# Ethernet.net
KiCad netlist of a schematic drawn in Altium Designer
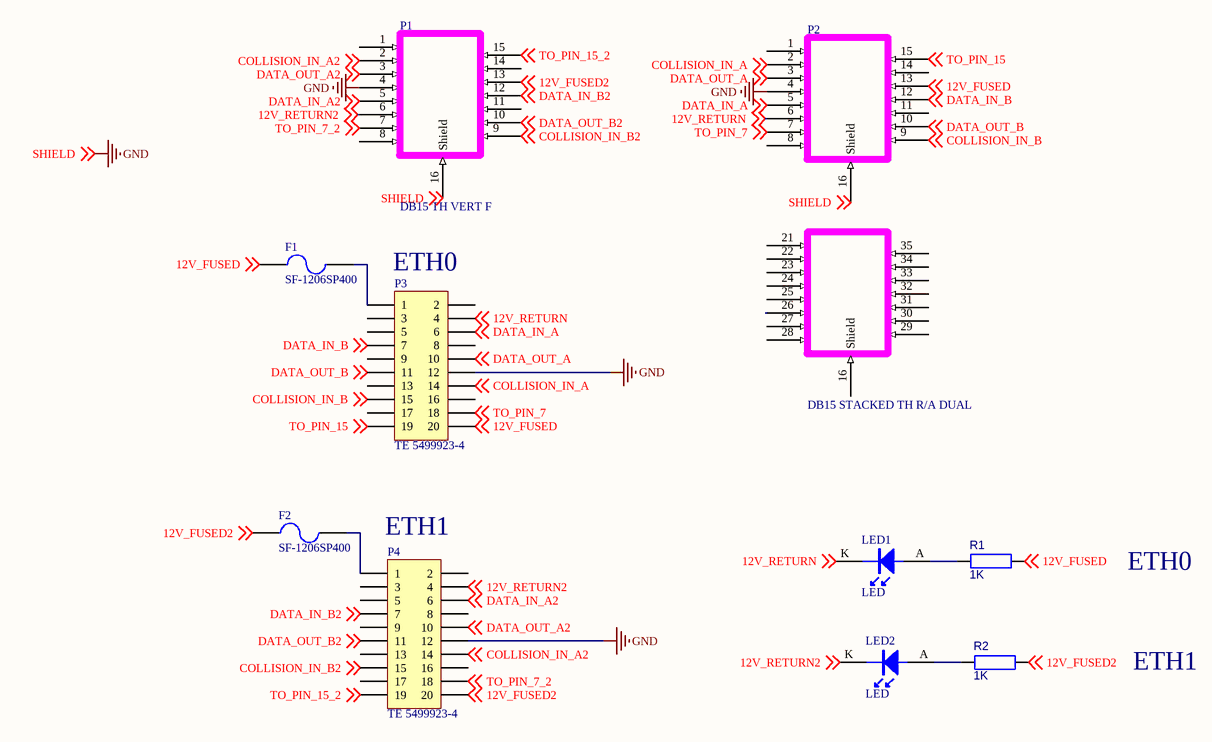
[diagram p0: Ethernet.SchDoc]

(export (version "E")
  (design (tool "Eeschema 10.0.6"))
  (components
    (comp (ref "F1")
      (value "SF-1206SP400")
      (footprint "F1206SB")
      (description "Fuse 4A")
      (fields (field (name "PUBLISHER") "Altium Limited"))
      (libsource (lib "Kanitti") (part "Fuse 2"))
    )
    (comp (ref "F2")
      (value "SF-1206SP400")
      (footprint "F1206SB")
      (description "Fuse 4A")
      (fields (field (name "PUBLISHER") "Altium Limited"))
      (libsource (lib "Kanitti") (part "Fuse 2"))
    )
    (comp (ref "LED1") (value "LED") (footprint "LTST-C170") (libsource (lib "TRA1404(DIFT2)") (part "LED")))
    (comp (ref "LED2") (value "LED") (footprint "LTST-C170") (libsource (lib "TRA1404(DIFT2)") (part "LED")))
    (comp (ref "P1")
      (value "DB15 TH VERT F")
      (footprint "D15S24A4GV00LF")
      (libsource (lib "Kanitti") (part "DB15 TH VERT F"))
    )
    (comp (ref "P2")
      (value "DB15 STACKED TH R/A DUAL")
      (footprint "189-015-513R571")
      (libsource (lib "Kanitti") (part "DB15 STACKED TH R/A DUAL"))
    )
    (comp (ref "P3")
      (value "TE 5499923-4")
      (footprint "HDR2X10 - Small Pads")
      (description "Header, 20-Pin, Dual row")
      (fields (field (name "PUBLISHER") "Altium Limited"))
      (libsource (lib "Kanitti") (part "Header 10X2"))
    )
    (comp (ref "P4")
      (value "TE 5499923-4")
      (footprint "HDR2X10 - Small Pads")
      (description "Header, 20-Pin, Dual row")
      (fields (field (name "PUBLISHER") "Altium Limited"))
      (libsource (lib "Kanitti") (part "Header 10X2"))
    )
    (comp (ref "R1")
      (value "1K")
      (footprint "RESC2012X70N")
      (description "RESISTOR")
      (libsource (lib "SCH") (part "RES2"))
    )
    (comp (ref "R2")
      (value "1K")
      (footprint "RESC2012X70N")
      (description "RESISTOR")
      (libsource (lib "SCH") (part "RES2"))
    )
  )
  (nets
    (net (code "1") (name "12V_FUSED") (class "Default")
      (node (ref "F1") (pin "1") (pinfunction "1_1") (pintype "passive"))
      (node (ref "P2") (pin "13") (pintype "input"))
      (node (ref "P3") (pin "20") (pinfunction "20_20") (pintype "passive"))
      (node (ref "R1") (pin "1") (pintype "passive"))
    )
    (net (code "2") (name "12V_FUSED2") (class "Default")
      (node (ref "F2") (pin "1") (pinfunction "1_1") (pintype "passive"))
      (node (ref "P1") (pin "13") (pintype "input"))
      (node (ref "P4") (pin "20") (pinfunction "20_20") (pintype "passive"))
      (node (ref "R2") (pin "1") (pintype "passive"))
    )
    (net (code "3") (name "12V_RETURN") (class "Default")
      (node (ref "LED1") (pin "K") (pinfunction "1_K") (pintype "passive"))
      (node (ref "P2") (pin "6") (pintype "input"))
      (node (ref "P3") (pin "4") (pinfunction "4_4") (pintype "passive"))
    )
    (net (code "4") (name "12V_RETURN2") (class "Default")
      (node (ref "LED2") (pin "K") (pinfunction "1_K") (pintype "passive"))
      (node (ref "P1") (pin "6") (pintype "input"))
      (node (ref "P4") (pin "4") (pinfunction "4_4") (pintype "passive"))
    )
    (net (code "5") (name "COLLISION_IN_A") (class "Default")
      (node (ref "P2") (pin "2") (pintype "input"))
      (node (ref "P3") (pin "14") (pinfunction "14_14") (pintype "passive"))
    )
    (net (code "6") (name "COLLISION_IN_A2") (class "Default")
      (node (ref "P1") (pin "2") (pintype "input"))
      (node (ref "P4") (pin "14") (pinfunction "14_14") (pintype "passive"))
    )
    (net (code "7") (name "COLLISION_IN_B") (class "Default")
      (node (ref "P2") (pin "9") (pintype "input"))
      (node (ref "P3") (pin "15") (pinfunction "15_15") (pintype "passive"))
    )
    (net (code "8") (name "COLLISION_IN_B2") (class "Default")
      (node (ref "P1") (pin "9") (pintype "input"))
      (node (ref "P4") (pin "15") (pinfunction "15_15") (pintype "passive"))
    )
    (net (code "9") (name "DATA_IN_A") (class "Default")
      (node (ref "P2") (pin "5") (pintype "input"))
      (node (ref "P3") (pin "6") (pinfunction "6_6") (pintype "passive"))
    )
    (net (code "10") (name "DATA_IN_A2") (class "Default")
      (node (ref "P1") (pin "5") (pintype "input"))
      (node (ref "P4") (pin "6") (pinfunction "6_6") (pintype "passive"))
    )
    (net (code "11") (name "DATA_IN_B") (class "Default")
      (node (ref "P2") (pin "12") (pintype "input"))
      (node (ref "P3") (pin "7") (pinfunction "7_7") (pintype "passive"))
    )
    (net (code "12") (name "DATA_IN_B2") (class "Default")
      (node (ref "P1") (pin "12") (pintype "input"))
      (node (ref "P4") (pin "7") (pinfunction "7_7") (pintype "passive"))
    )
    (net (code "13") (name "DATA_OUT_A") (class "Default")
      (node (ref "P2") (pin "3") (pintype "input"))
      (node (ref "P3") (pin "10") (pinfunction "10_10") (pintype "passive"))
    )
    (net (code "14") (name "DATA_OUT_A2") (class "Default")
      (node (ref "P1") (pin "3") (pintype "input"))
      (node (ref "P4") (pin "10") (pinfunction "10_10") (pintype "passive"))
    )
    (net (code "15") (name "DATA_OUT_B") (class "Default")
      (node (ref "P2") (pin "10") (pintype "input"))
      (node (ref "P3") (pin "11") (pinfunction "11_11") (pintype "passive"))
    )
    (net (code "16") (name "DATA_OUT_B2") (class "Default")
      (node (ref "P1") (pin "10") (pintype "input"))
      (node (ref "P4") (pin "11") (pinfunction "11_11") (pintype "passive"))
    )
    (net (code "17") (name "GND") (class "Default")
      (node (ref "P1") (pin "16") (pinfunction "Shield_16") (pintype "input"))
      (node (ref "P1") (pin "4") (pintype "input"))
      (node (ref "P2") (pin "16") (pinfunction "Shield_16") (pintype "input"))
      (node (ref "P2") (pin "4") (pintype "input"))
      (node (ref "P3") (pin "12") (pinfunction "12_12") (pintype "passive"))
      (node (ref "P4") (pin "12") (pinfunction "12_12") (pintype "passive"))
    )
    (net (code "18") (name "Net-(F1-Pad2)") (class "Default")
      (node (ref "F1") (pin "2") (pinfunction "2_2") (pintype "passive"))
      (node (ref "P3") (pin "1") (pinfunction "1_1") (pintype "passive"))
    )
    (net (code "19") (name "Net-(F2-Pad2)") (class "Default")
      (node (ref "F2") (pin "2") (pinfunction "2_2") (pintype "passive"))
      (node (ref "P4") (pin "1") (pinfunction "1_1") (pintype "passive"))
    )
    (net (code "20") (name "Net-(LED1-2)") (class "Default")
      (node (ref "LED1") (pin "A") (pinfunction "2_A") (pintype "passive"))
      (node (ref "R1") (pin "2") (pintype "passive"))
    )
    (net (code "21") (name "Net-(LED2-2)") (class "Default")
      (node (ref "LED2") (pin "A") (pinfunction "2_A") (pintype "passive"))
      (node (ref "R2") (pin "2") (pintype "passive"))
    )
    (net (code "22") (name "TO_PIN_7") (class "Default")
      (node (ref "P2") (pin "7") (pintype "input"))
      (node (ref "P3") (pin "18") (pinfunction "18_18") (pintype "passive"))
    )
    (net (code "23") (name "TO_PIN_7_2") (class "Default")
      (node (ref "P1") (pin "7") (pintype "input"))
      (node (ref "P4") (pin "18") (pinfunction "18_18") (pintype "passive"))
    )
    (net (code "24") (name "TO_PIN_15") (class "Default")
      (node (ref "P2") (pin "15") (pintype "input"))
      (node (ref "P3") (pin "19") (pinfunction "19_19") (pintype "passive"))
    )
    (net (code "25") (name "TO_PIN_15_2") (class "Default")
      (node (ref "P1") (pin "15") (pintype "input"))
      (node (ref "P4") (pin "19") (pinfunction "19_19") (pintype "passive"))
    )
    (net (code "26") (name "unconnected-(P1-Pad1)") (class "Default")
      (node (ref "P1") (pin "1") (pintype "input"))
    )
    (net (code "27") (name "unconnected-(P1-Pad8)") (class "Default")
      (node (ref "P1") (pin "8") (pintype "input"))
    )
    (net (code "28") (name "unconnected-(P1-Pad11)") (class "Default")
      (node (ref "P1") (pin "11") (pintype "input"))
    )
    (net (code "29") (name "unconnected-(P1-Pad14)") (class "Default")
      (node (ref "P1") (pin "14") (pintype "input"))
    )
    (net (code "30") (name "unconnected-(P2-Pad1)") (class "Default")
      (node (ref "P2") (pin "1") (pintype "input"))
    )
    (net (code "31") (name "unconnected-(P2-Pad8)") (class "Default")
      (node (ref "P2") (pin "8") (pintype "input"))
    )
    (net (code "32") (name "unconnected-(P2-Pad11)") (class "Default")
      (node (ref "P2") (pin "11") (pintype "input"))
    )
    (net (code "33") (name "unconnected-(P2-Pad14)") (class "Default")
      (node (ref "P2") (pin "14") (pintype "input"))
    )
    (net (code "34") (name "unconnected-(P2-Pad21)") (class "Default")
      (node (ref "P2") (pin "21") (pintype "input"))
    )
    (net (code "35") (name "unconnected-(P2-Pad22)") (class "Default")
      (node (ref "P2") (pin "22") (pintype "input"))
    )
    (net (code "36") (name "unconnected-(P2-Pad23)") (class "Default")
      (node (ref "P2") (pin "23") (pintype "input"))
    )
    (net (code "37") (name "unconnected-(P2-Pad24)") (class "Default")
      (node (ref "P2") (pin "24") (pintype "input"))
    )
    (net (code "38") (name "unconnected-(P2-Pad25)") (class "Default")
      (node (ref "P2") (pin "25") (pintype "input"))
    )
    (net (code "39") (name "unconnected-(P2-Pad26)") (class "Default")
      (node (ref "P2") (pin "26") (pintype "input"))
    )
    (net (code "40") (name "unconnected-(P2-Pad27)") (class "Default")
      (node (ref "P2") (pin "27") (pintype "input"))
    )
    (net (code "41") (name "unconnected-(P2-Pad28)") (class "Default")
      (node (ref "P2") (pin "28") (pintype "input"))
    )
    (net (code "42") (name "unconnected-(P2-Pad29)") (class "Default")
      (node (ref "P2") (pin "29") (pintype "input"))
    )
    (net (code "43") (name "unconnected-(P2-Pad30)") (class "Default")
      (node (ref "P2") (pin "30") (pintype "input"))
    )
    (net (code "44") (name "unconnected-(P2-Pad31)") (class "Default")
      (node (ref "P2") (pin "31") (pintype "input"))
    )
    (net (code "45") (name "unconnected-(P2-Pad32)") (class "Default")
      (node (ref "P2") (pin "32") (pintype "input"))
    )
    (net (code "46") (name "unconnected-(P2-Pad33)") (class "Default")
      (node (ref "P2") (pin "33") (pintype "input"))
    )
    (net (code "47") (name "unconnected-(P2-Pad34)") (class "Default")
      (node (ref "P2") (pin "34") (pintype "input"))
    )
    (net (code "48") (name "unconnected-(P2-Pad35)") (class "Default")
      (node (ref "P2") (pin "35") (pintype "input"))
    )
    (net (code "49") (name "unconnected-(P2-Shield-Pad16)") (class "Default")
      (node (ref "P2") (pin "16") (pinfunction "Shield_16") (pintype "input"))
    )
    (net (code "50") (name "unconnected-(P3-Pad2)") (class "Default")
      (node (ref "P3") (pin "2") (pinfunction "2_2") (pintype "passive"))
    )
    (net (code "51") (name "unconnected-(P3-Pad3)") (class "Default")
      (node (ref "P3") (pin "3") (pinfunction "3_3") (pintype "passive"))
    )
    (net (code "52") (name "unconnected-(P3-Pad5)") (class "Default")
      (node (ref "P3") (pin "5") (pinfunction "5_5") (pintype "passive"))
    )
    (net (code "53") (name "unconnected-(P3-Pad8)") (class "Default")
      (node (ref "P3") (pin "8") (pinfunction "8_8") (pintype "passive"))
    )
    (net (code "54") (name "unconnected-(P3-Pad9)") (class "Default")
      (node (ref "P3") (pin "9") (pinfunction "9_9") (pintype "passive"))
    )
    (net (code "55") (name "unconnected-(P3-Pad13)") (class "Default")
      (node (ref "P3") (pin "13") (pinfunction "13_13") (pintype "passive"))
    )
    (net (code "56") (name "unconnected-(P3-Pad16)") (class "Default")
      (node (ref "P3") (pin "16") (pinfunction "16_16") (pintype "passive"))
    )
    (net (code "57") (name "unconnected-(P3-Pad17)") (class "Default")
      (node (ref "P3") (pin "17") (pinfunction "17_17") (pintype "passive"))
    )
    (net (code "58") (name "unconnected-(P4-Pad2)") (class "Default")
      (node (ref "P4") (pin "2") (pinfunction "2_2") (pintype "passive"))
    )
    (net (code "59") (name "unconnected-(P4-Pad3)") (class "Default")
      (node (ref "P4") (pin "3") (pinfunction "3_3") (pintype "passive"))
    )
    (net (code "60") (name "unconnected-(P4-Pad5)") (class "Default")
      (node (ref "P4") (pin "5") (pinfunction "5_5") (pintype "passive"))
    )
    (net (code "61") (name "unconnected-(P4-Pad8)") (class "Default")
      (node (ref "P4") (pin "8") (pinfunction "8_8") (pintype "passive"))
    )
    (net (code "62") (name "unconnected-(P4-Pad9)") (class "Default")
      (node (ref "P4") (pin "9") (pinfunction "9_9") (pintype "passive"))
    )
    (net (code "63") (name "unconnected-(P4-Pad13)") (class "Default")
      (node (ref "P4") (pin "13") (pinfunction "13_13") (pintype "passive"))
    )
    (net (code "64") (name "unconnected-(P4-Pad16)") (class "Default")
      (node (ref "P4") (pin "16") (pinfunction "16_16") (pintype "passive"))
    )
    (net (code "65") (name "unconnected-(P4-Pad17)") (class "Default")
      (node (ref "P4") (pin "17") (pinfunction "17_17") (pintype "passive"))
    )
  )
)
